# BigButtons.net
KiCad netlist of a schematic drawn in Altium Designer
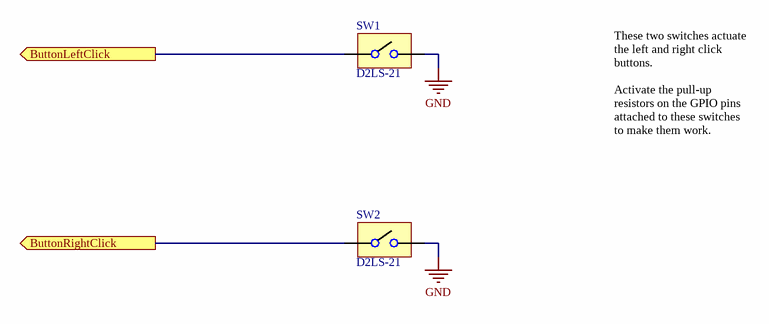
[diagram p0: BigButtons.SchDoc]

(export (version "E")
  (design (tool "Eeschema 10.0.6"))
  (components
    (comp (ref "SW1")
      (value "D2LS-21")
      (footprint "D2LS-21")
      (description "Compact Surface-mounting Switch for long durability")
      (libsource (lib "Switches") (part "D2LS-21"))
    )
    (comp (ref "SW2")
      (value "D2LS-21")
      (footprint "D2LS-21")
      (description "Compact Surface-mounting Switch for long durability")
      (libsource (lib "Switches") (part "D2LS-21"))
    )
  )
  (nets
    (net (code "1") (name "/ButtonLeftClick") (class "Default")
      (node (ref "SW1") (pin "A") (pinfunction "A_A") (pintype "passive"))
    )
    (net (code "2") (name "/ButtonRightClick") (class "Default")
      (node (ref "SW2") (pin "A") (pinfunction "A_A") (pintype "passive"))
    )
    (net (code "3") (name "GND") (class "Default")
      (node (ref "SW1") (pin "B") (pinfunction "B_B") (pintype "passive"))
      (node (ref "SW2") (pin "B") (pinfunction "B_B") (pintype "passive"))
    )
  )
)
